# 06_Memories.net
KiCad netlist of a schematic drawn in Altium Designer
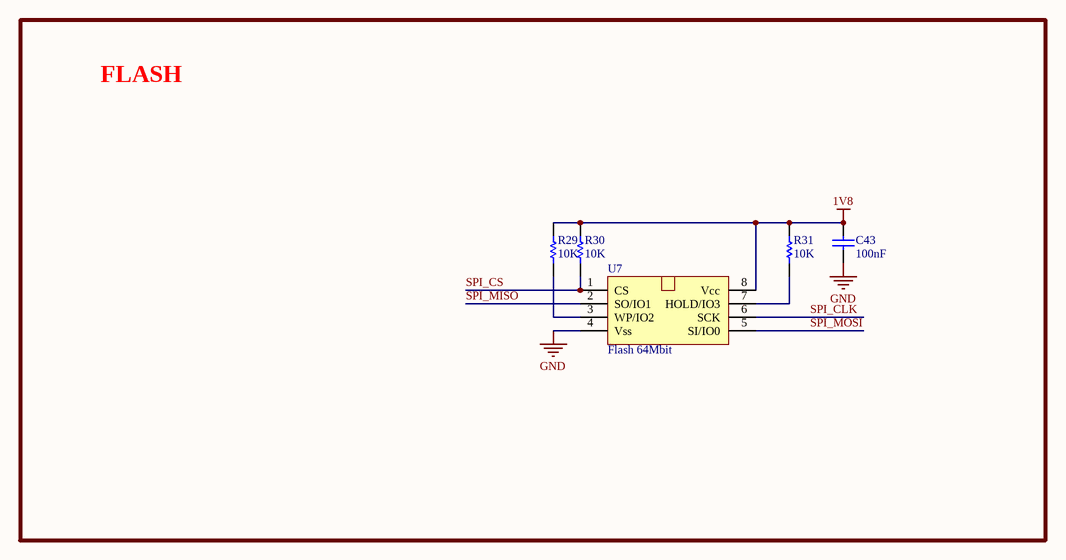
[diagram p0: 06 Memories.SchDoc]

(export (version "E")
  (design (tool "Eeschema 10.0.6"))
  (components
    (comp (ref "C43")
      (value "100nF")
      (footprint "0603 - C")
      (description "CAP CER 100nF 50V C0G/NP0 0603")
      (fields (field (name "VOLTAGE") "50V") (field (name "MPN") "CL10C104JB8NNNC"))
      (libsource (lib "Library_Chip") (part "Cap 0603 100nF"))
    )
    (comp (ref "R29")
      (value "10K")
      (footprint "0603 - R")
      (description "RES SMD 10K OHM 1% 1/10W 0603")
      (fields (field (name "MFR") "Yageo") (field (name "MPN") "RC0603FR-0710KL"))
      (libsource (lib "Library_Chip") (part "Res 0603 10K"))
    )
    (comp (ref "R30")
      (value "10K")
      (footprint "0603 - R")
      (description "RES SMD 10K OHM 1% 1/10W 0603")
      (fields (field (name "MFR") "Yageo") (field (name "MPN") "RC0603FR-0710KL"))
      (libsource (lib "Library_Chip") (part "Res 0603 10K"))
    )
    (comp (ref "R31")
      (value "10K")
      (footprint "0603 - R")
      (description "RES SMD 10K OHM 1% 1/10W 0603")
      (fields (field (name "MFR") "Yageo") (field (name "MPN") "RC0603FR-0710KL"))
      (libsource (lib "Library_Chip") (part "Res 0603 10K"))
    )
    (comp (ref "U7")
      (value "Flash 64Mbit")
      (footprint "8 - SOIC")
      (description "IC FLASH 64MBIT CMOS SPI 8SOIC 1.8V")
      (fields (field (name "MFR") "Gigadevice") (field (name "MPN") "GD25LQ64ESIGR"))
      (libsource (lib "Library_IC") (part "Flash 64Mb-1.8V"))
    )
  )
  (nets
    (net (code "1") (name "/SPI_CLK") (class "Default")
      (node (ref "U7") (pin "6") (pinfunction "SCK_6") (pintype "passive"))
    )
    (net (code "2") (name "/SPI_CS") (class "Default")
      (node (ref "R30") (pin "1") (pinfunction "1_1") (pintype "passive"))
      (node (ref "U7") (pin "1") (pinfunction "CS_1") (pintype "passive"))
    )
    (net (code "3") (name "/SPI_MISO") (class "Default")
      (node (ref "U7") (pin "2") (pinfunction "SO/IO1_2") (pintype "passive"))
    )
    (net (code "4") (name "/SPI_MOSI") (class "Default")
      (node (ref "U7") (pin "5") (pinfunction "SI/IO0_5") (pintype "passive"))
    )
    (net (code "5") (name "1V8") (class "Default")
      (node (ref "C43") (pin "2") (pinfunction "2_2") (pintype "passive"))
      (node (ref "R29") (pin "2") (pinfunction "2_2") (pintype "passive"))
      (node (ref "R30") (pin "2") (pinfunction "2_2") (pintype "passive"))
      (node (ref "R31") (pin "2") (pinfunction "2_2") (pintype "passive"))
      (node (ref "U7") (pin "8") (pinfunction "Vcc_8") (pintype "passive"))
    )
    (net (code "6") (name "GND") (class "Default")
      (node (ref "C43") (pin "1") (pinfunction "1_1") (pintype "passive"))
      (node (ref "U7") (pin "4") (pinfunction "Vss_4") (pintype "passive"))
    )
    (net (code "7") (name "Net-(U7-HOLD{slash}IO3)") (class "Default")
      (node (ref "R31") (pin "1") (pinfunction "1_1") (pintype "passive"))
      (node (ref "U7") (pin "7") (pinfunction "HOLD/IO3_7") (pintype "passive"))
    )
    (net (code "8") (name "Net-(U7-WP{slash}IO2)") (class "Default")
      (node (ref "R29") (pin "1") (pinfunction "1_1") (pintype "passive"))
      (node (ref "U7") (pin "3") (pinfunction "WP/IO2_3") (pintype "passive"))
    )
  )
)
